# Power.net
KiCad netlist of a schematic drawn in Altium Designer
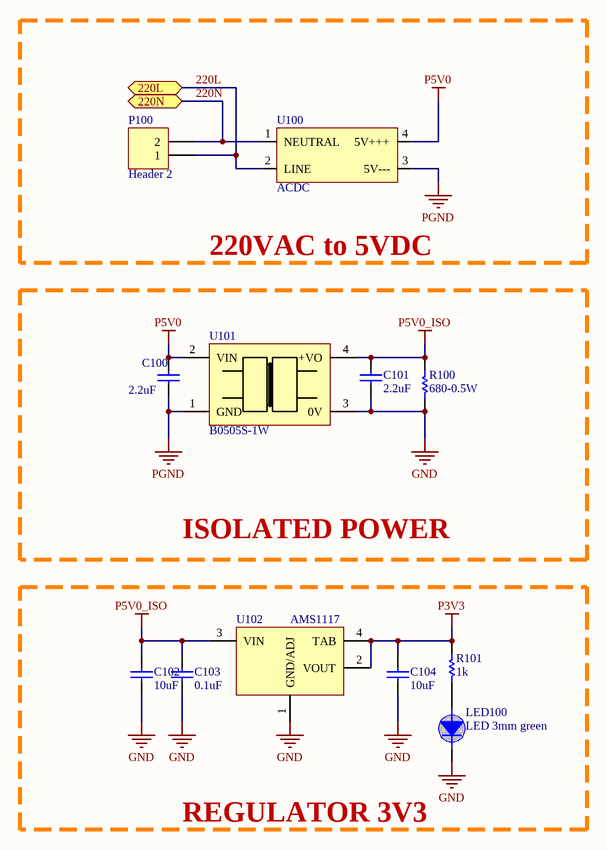
[diagram p0: Power.SchDoc]

(export (version "E")
  (design (tool "Eeschema 10.0.6"))
  (components
    (comp (ref "C100") (value "2.2uF") (footprint "0805 cap") (libsource (lib "BinhLib") (part "cap SMD")))
    (comp (ref "C101") (value "2.2uF") (footprint "0805 cap") (libsource (lib "BinhLib") (part "cap SMD")))
    (comp (ref "C102") (value "10uF") (footprint "0805 cap") (libsource (lib "BinhLib") (part "cap SMD")))
    (comp (ref "C103") (value "0.1uF") (footprint "0805 cap") (libsource (lib "BinhLib") (part "cap SMD")))
    (comp (ref "C104") (value "10uF") (footprint "0805 cap") (libsource (lib "BinhLib") (part "cap SMD")))
    (comp (ref "LED100")
      (value "LED 3mm green")
      (footprint "LED 3mm green")
      (libsource (lib "BinhLib") (part "LED 3mm green"))
    )
    (comp (ref "P100")
      (value "Header 2")
      (footprint "HED2T")
      (description "Header, 2-Pin")
      (fields (field (name "PUBLISHER") "Altium Limited"))
      (libsource (lib "BinhLib") (part "Header 2"))
    )
    (comp (ref "R100")
      (value "680-0.5W")
      (footprint "0805 Resistor")
      (libsource (lib "BinhLib") (part "Resistor"))
    )
    (comp (ref "R101") (value "1k") (footprint "0805 Resistor") (libsource (lib "BinhLib") (part "Resistor")))
    (comp (ref "U100") (value "ACDC") (footprint "ACDC") (libsource (lib "SFControl") (part "ACDC")))
    (comp (ref "U101")
      (value "B0505S-1W")
      (footprint "B0505S-1W")
      (libsource (lib "LiquidFilter") (part "B0505S-1W"))
    )
    (comp (ref "U102") (value "AMS1117") (footprint "SOT223-3") (libsource (lib "BinhLib") (part "AMS1117")))
  )
  (nets
    (net (code "1") (name "/220L") (class "Default")
      (node (ref "P100") (pin "1") (pinfunction "1_1") (pintype "passive"))
      (node (ref "U100") (pin "2") (pinfunction "LINE_2") (pintype "passive"))
    )
    (net (code "2") (name "/220N") (class "Default")
      (node (ref "P100") (pin "2") (pinfunction "2_2") (pintype "passive"))
      (node (ref "U100") (pin "1") (pinfunction "NEUTRAL_1") (pintype "passive"))
    )
    (net (code "3") (name "GND") (class "Default")
      (node (ref "C101") (pin "1") (pintype "passive"))
      (node (ref "C102") (pin "1") (pintype "passive"))
      (node (ref "C103") (pin "1") (pintype "passive"))
      (node (ref "C104") (pin "1") (pintype "passive"))
      (node (ref "LED100") (pin "2") (pinfunction "Katot_2") (pintype "passive"))
      (node (ref "R100") (pin "1") (pinfunction "1_1") (pintype "passive"))
      (node (ref "U101") (pin "3") (pinfunction "0V_3") (pintype "passive"))
      (node (ref "U102") (pin "1") (pinfunction "GND/ADJ_1") (pintype "passive"))
    )
    (net (code "4") (name "Net-(LED100-anot)") (class "Default")
      (node (ref "LED100") (pin "1") (pinfunction "anot_1") (pintype "passive"))
      (node (ref "R101") (pin "1") (pinfunction "1_1") (pintype "passive"))
    )
    (net (code "5") (name "P3V3") (class "Default")
      (node (ref "C104") (pin "2") (pintype "passive"))
      (node (ref "R101") (pin "2") (pinfunction "2_2") (pintype "passive"))
      (node (ref "U102") (pin "2") (pinfunction "VOUT_2") (pintype "passive"))
      (node (ref "U102") (pin "4") (pinfunction "TAB_4") (pintype "passive"))
    )
    (net (code "6") (name "P5V0") (class "Default")
      (node (ref "C100") (pin "2") (pintype "passive"))
      (node (ref "U100") (pin "4") (pinfunction "5V+++_4") (pintype "passive"))
      (node (ref "U101") (pin "2") (pinfunction "VIN_2") (pintype "passive"))
    )
    (net (code "7") (name "P5V0_ISO") (class "Default")
      (node (ref "C101") (pin "2") (pintype "passive"))
      (node (ref "C102") (pin "2") (pintype "passive"))
      (node (ref "C103") (pin "2") (pintype "passive"))
      (node (ref "R100") (pin "2") (pinfunction "2_2") (pintype "passive"))
      (node (ref "U101") (pin "4") (pinfunction "+VO_4") (pintype "passive"))
      (node (ref "U102") (pin "3") (pinfunction "VIN_3") (pintype "passive"))
    )
    (net (code "8") (name "PGND") (class "Default")
      (node (ref "C100") (pin "1") (pintype "passive"))
      (node (ref "U100") (pin "3") (pinfunction "5V---_3") (pintype "passive"))
      (node (ref "U101") (pin "1") (pinfunction "GND_1") (pintype "passive"))
    )
  )
)
